# USB_Isolation.net
KiCad netlist of a schematic drawn in Altium Designer
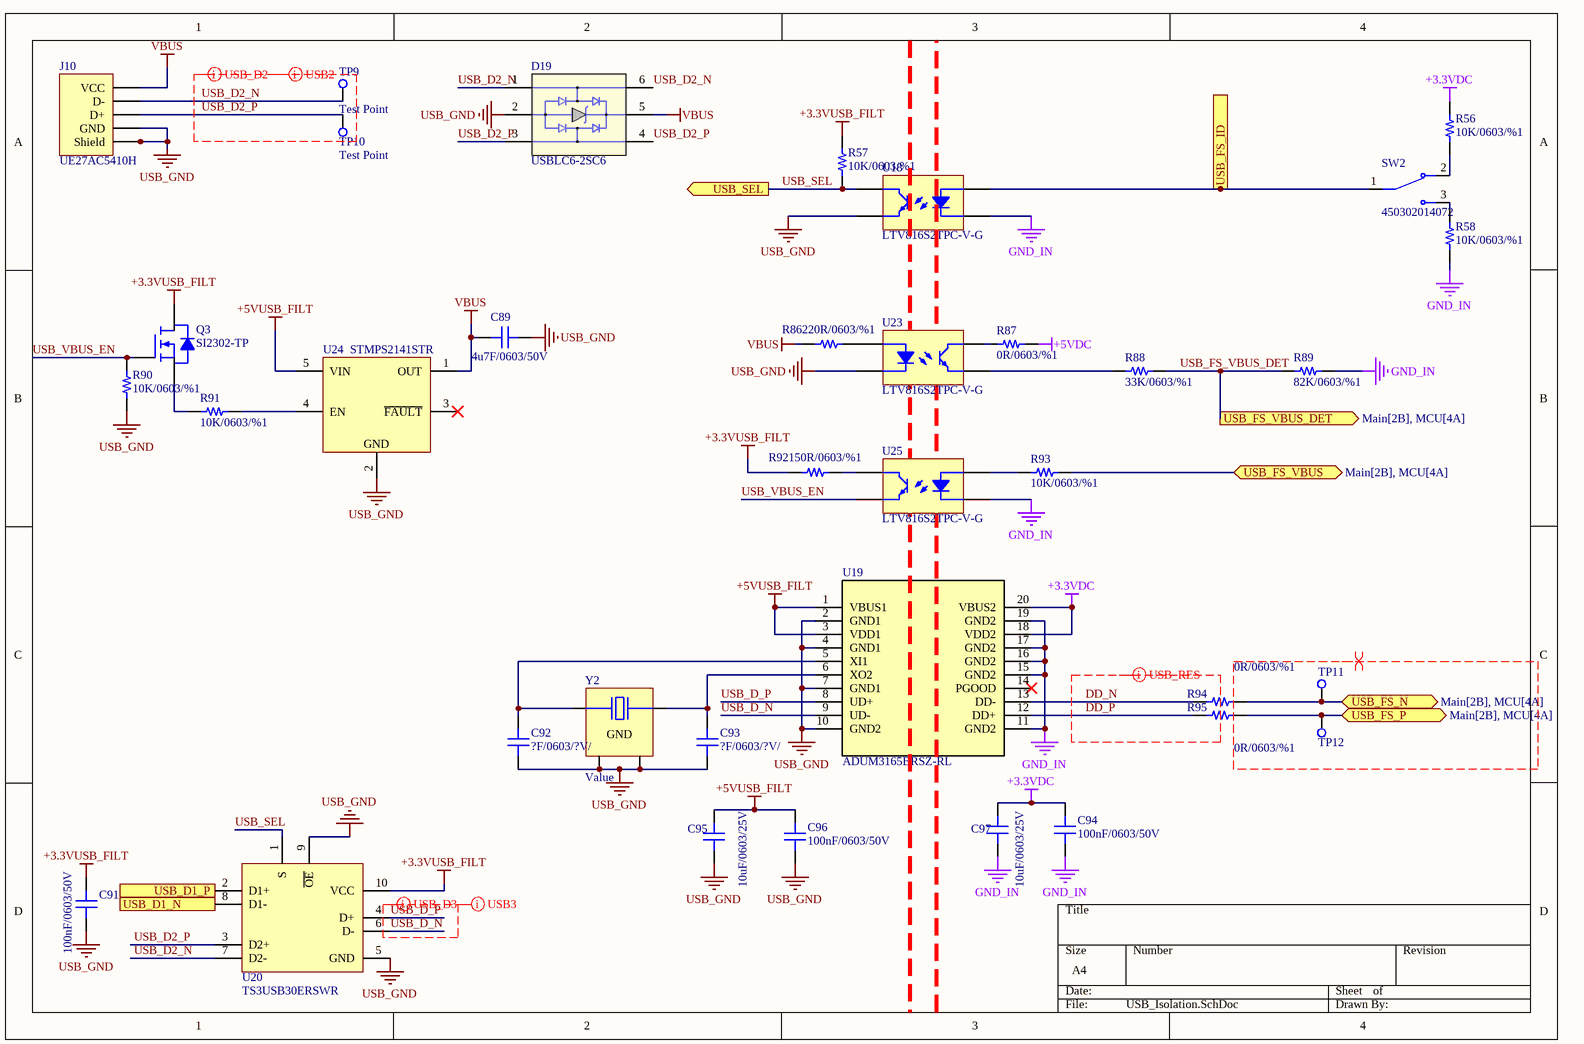
[diagram p0: USB_Isolation.SchDoc]

(export (version "E")
  (design (tool "Eeschema 10.0.6"))
  (components
    (comp (ref "C89")
      (value "4u7F/0603/50V")
      (footprint "0603_cap")
      (libsource (lib "IM_v1.0") (part "Capacitor"))
    )
    (comp (ref "C91")
      (value "100nF/0603/50V")
      (footprint "0603_cap")
      (libsource (lib "IM_v1.0") (part "Capacitor"))
    )
    (comp (ref "C92")
      (value "?F/0603/?V/")
      (footprint "0603_cap")
      (libsource (lib "IM_v1.0") (part "Capacitor"))
    )
    (comp (ref "C93")
      (value "?F/0603/?V/")
      (footprint "0603_cap")
      (libsource (lib "IM_v1.0") (part "Capacitor"))
    )
    (comp (ref "C94")
      (value "100nF/0603/50V")
      (footprint "0603_cap")
      (libsource (lib "IM_v1.0") (part "Capacitor"))
    )
    (comp (ref "C95")
      (value "10uF/0603/25V")
      (footprint "0603_cap")
      (libsource (lib "IM_v1.0") (part "Capacitor"))
    )
    (comp (ref "C96")
      (value "100nF/0603/50V")
      (footprint "0603_cap")
      (libsource (lib "IM_v1.0") (part "Capacitor"))
    )
    (comp (ref "C97")
      (value "10uF/0603/25V")
      (footprint "0603_cap")
      (libsource (lib "IM_v1.0") (part "Capacitor"))
    )
    (comp (ref "D19")
      (value "USBLC6-2SC6")
      (footprint "TI SOT-23-6 DBV")
      (description "17V Clamp 5A (8/20µs) Ipp Tvs Diode Surface Mount SOT-23-6")
      (libsource (lib "IM_v1.0") (part "USBLC6-2SC6"))
    )
    (comp (ref "J10")
      (value "UE27AC5410H")
      (footprint "UE27AC5410H")
      (libsource (lib "IM_v1.0") (part "USB 2.0 TYPE A"))
    )
    (comp (ref "Q3")
      (value "SI2302-TP")
      (footprint "TI SOT-23-3 DBZ")
      (description "MOSFET N-CH 20V 3A SOT-23")
      (libsource (lib "IM_v1.0") (part "N-CHN MOS SOT"))
    )
    (comp (ref "R56") (value "10K/0603/%1") (footprint "0603_res") (libsource (lib "IM_v1.0") (part "RES")))
    (comp (ref "R57") (value "10K/0603/%1") (footprint "0603_res") (libsource (lib "IM_v1.0") (part "RES")))
    (comp (ref "R58") (value "10K/0603/%1") (footprint "0603_res") (libsource (lib "IM_v1.0") (part "RES")))
    (comp (ref "R86") (value "220R/0603/%1") (footprint "0603_res") (libsource (lib "IM_v1.0") (part "RES")))
    (comp (ref "R87") (value "0R/0603/%1") (footprint "0603_res") (libsource (lib "IM_v1.0") (part "RES")))
    (comp (ref "R88") (value "33K/0603/%1") (footprint "0603_res") (libsource (lib "IM_v1.0") (part "RES")))
    (comp (ref "R89") (value "82K/0603/%1") (footprint "0603_res") (libsource (lib "IM_v1.0") (part "RES")))
    (comp (ref "R90") (value "10K/0603/%1") (footprint "0603_res") (libsource (lib "IM_v1.0") (part "RES")))
    (comp (ref "R91") (value "10K/0603/%1") (footprint "0603_res") (libsource (lib "IM_v1.0") (part "RES")))
    (comp (ref "R92") (value "150R/0603/%1") (footprint "0603_res") (libsource (lib "IM_v1.0") (part "RES")))
    (comp (ref "R93") (value "10K/0603/%1") (footprint "0603_res") (libsource (lib "IM_v1.0") (part "RES")))
    (comp (ref "R94") (value "0R/0603/%1") (footprint "0603_res") (libsource (lib "IM_v1.0") (part "RES")))
    (comp (ref "R95") (value "0R/0603/%1") (footprint "0603_res") (libsource (lib "IM_v1.0") (part "RES")))
    (comp (ref "SW2")
      (value "450302014072")
      (footprint "450302014072")
      (libsource (lib "IM_v1.0") (part "SPDT"))
    )
    (comp (ref "TP9") (value "Test Point") (footprint "tp") (libsource (lib "IM_v1.0") (part "Test Point")))
    (comp (ref "TP10") (value "Test Point") (footprint "tp") (libsource (lib "IM_v1.0") (part "Test Point")))
    (comp (ref "TP11") (value "Test Point") (footprint "tp") (libsource (lib "IM_v1.0") (part "Test Point")))
    (comp (ref "TP12") (value "Test Point") (footprint "tp") (libsource (lib "IM_v1.0") (part "Test Point")))
    (comp (ref "U18")
      (value "LTV816S2TPC-V-G")
      (footprint "4-SMD, Gull Wing")
      (libsource (lib "IM_v1.0") (part "OPTO"))
    )
    (comp (ref "U19")
      (value "ADUM3165BRSZ-RL")
      (footprint "SSOP-20")
      (description "3.75 kV RMS Digital Isolators for Isolated USB 2.0 High, Full, and Low Speed")
      (libsource (lib "IM_v1.0") (part "ADUM3165"))
    )
    (comp (ref "U20")
      (value "TS3USB30ERSWR")
      (footprint "VSSOP-10")
      (libsource (lib "IM_v1.0") (part "TS3USB30ERSWR"))
    )
    (comp (ref "U23")
      (value "LTV816S2TPC-V-G")
      (footprint "4-SMD, Gull Wing")
      (libsource (lib "") (part "OPTO_1"))
    )
    (comp (ref "U24")
      (value "STMPS2141STR")
      (footprint "SOT-23-5")
      (description "IC PWR SWITCH N-CHAN 1:1 SOT23-5")
      (fields (field (name "MANUFACTURER") "STMicroelectronics"))
      (libsource (lib "IM_v1.0") (part "STMPS2141STR"))
    )
    (comp (ref "U25")
      (value "LTV816S2TPC-V-G")
      (footprint "4-SMD, Gull Wing")
      (libsource (lib "IM_v1.0") (part "OPTO"))
    )
    (comp (ref "Y2")
      (value "Value")
      (footprint "SMD4-Nolead")
      (description "25 MHz ±10ppm Crystal 10pF 50 Ohms 4-SMD, No Lead")
      (libsource (lib "IM_v1.0") (part "Crystal(4-SMD)"))
    )
  )
  (nets
    (net (code "1") (name "+3.3VDC") (class "Default")
      (node (ref "C94") (pin "2") (pinfunction "2_2") (pintype "passive"))
      (node (ref "C97") (pin "2") (pinfunction "2_2") (pintype "passive"))
      (node (ref "R56") (pin "1") (pinfunction "1_1") (pintype "passive"))
      (node (ref "U19") (pin "18") (pinfunction "VDD2_18") (pintype "passive"))
      (node (ref "U19") (pin "20") (pinfunction "VBUS2_20") (pintype "passive"))
    )
    (net (code "2") (name "+3.3VUSB_FILT") (class "Default")
      (node (ref "C91") (pin "1") (pinfunction "1_1") (pintype "passive"))
      (node (ref "Q3") (pin "3") (pinfunction "D_3") (pintype "passive"))
      (node (ref "R57") (pin "1") (pinfunction "1_1") (pintype "passive"))
      (node (ref "R92") (pin "1") (pinfunction "1_1") (pintype "passive"))
      (node (ref "U20") (pin "10") (pinfunction "VCC_10") (pintype "passive"))
    )
    (net (code "3") (name "+5VDC") (class "Default")
      (node (ref "R87") (pin "1") (pinfunction "1_1") (pintype "passive"))
    )
    (net (code "4") (name "+5VUSB_FILT") (class "Default")
      (node (ref "C95") (pin "2") (pinfunction "2_2") (pintype "passive"))
      (node (ref "C96") (pin "2") (pinfunction "2_2") (pintype "passive"))
      (node (ref "U19") (pin "1") (pinfunction "VBUS1_1") (pintype "passive"))
      (node (ref "U19") (pin "3") (pinfunction "VDD1_3") (pintype "passive"))
      (node (ref "U24") (pin "5") (pinfunction "VIN_5") (pintype "passive"))
    )
    (net (code "5") (name "/DD_N") (class "Default")
      (node (ref "R94") (pin "2") (pinfunction "2_2") (pintype "passive"))
      (node (ref "U19") (pin "13") (pinfunction "DD-_13") (pintype "passive"))
    )
    (net (code "6") (name "/DD_P") (class "Default")
      (node (ref "R95") (pin "2") (pinfunction "2_2") (pintype "passive"))
      (node (ref "U19") (pin "12") (pinfunction "DD+_12") (pintype "passive"))
    )
    (net (code "7") (name "/USB_D1_N") (class "Default")
      (node (ref "U20") (pin "8") (pinfunction "D1-_8") (pintype "passive"))
    )
    (net (code "8") (name "/USB_D1_P") (class "Default")
      (node (ref "U20") (pin "2") (pinfunction "D1+_2") (pintype "passive"))
    )
    (net (code "9") (name "/USB_D2_N") (class "Default")
      (node (ref "D19") (pin "1") (pinfunction "1_1") (pintype "passive"))
      (node (ref "D19") (pin "6") (pinfunction "6_6") (pintype "passive"))
      (node (ref "J10") (pin "02") (pinfunction "D-_02") (pintype "passive"))
      (node (ref "TP9") (pin "1") (pinfunction "TP_1") (pintype "passive"))
      (node (ref "U20") (pin "7") (pinfunction "D2-_7") (pintype "passive"))
    )
    (net (code "10") (name "/USB_D2_P") (class "Default")
      (node (ref "D19") (pin "3") (pinfunction "3_3") (pintype "passive"))
      (node (ref "D19") (pin "4") (pinfunction "4_4") (pintype "passive"))
      (node (ref "J10") (pin "03") (pinfunction "D+_03") (pintype "passive"))
      (node (ref "TP10") (pin "1") (pinfunction "TP_1") (pintype "passive"))
      (node (ref "U20") (pin "3") (pinfunction "D2+_3") (pintype "passive"))
    )
    (net (code "11") (name "/USB_D_N") (class "Default")
      (node (ref "U19") (pin "9") (pinfunction "UD-_9") (pintype "passive"))
      (node (ref "U20") (pin "6") (pinfunction "D-_6") (pintype "passive"))
    )
    (net (code "12") (name "/USB_D_P") (class "Default")
      (node (ref "U19") (pin "8") (pinfunction "UD+_8") (pintype "passive"))
      (node (ref "U20") (pin "4") (pinfunction "D+_4") (pintype "passive"))
    )
    (net (code "13") (name "/USB_FS_ID") (class "Default")
      (node (ref "SW2") (pin "1") (pinfunction "1_1") (pintype "passive"))
      (node (ref "U18") (pin "1") (pinfunction "1_1") (pintype "passive"))
    )
    (net (code "14") (name "/USB_FS_N") (class "Default")
      (node (ref "R94") (pin "1") (pinfunction "1_1") (pintype "passive"))
      (node (ref "TP11") (pin "1") (pinfunction "TP_1") (pintype "passive"))
    )
    (net (code "15") (name "/USB_FS_P") (class "Default")
      (node (ref "R95") (pin "1") (pinfunction "1_1") (pintype "passive"))
      (node (ref "TP12") (pin "1") (pinfunction "TP_1") (pintype "passive"))
    )
    (net (code "16") (name "/USB_FS_VBUS") (class "Default")
      (node (ref "R93") (pin "1") (pinfunction "1_1") (pintype "passive"))
    )
    (net (code "17") (name "/USB_FS_VBUS_DET") (class "Default")
      (node (ref "R88") (pin "2") (pinfunction "2_2") (pintype "passive"))
      (node (ref "R89") (pin "1") (pinfunction "1_1") (pintype "passive"))
    )
    (net (code "18") (name "/USB_SEL") (class "Default")
      (node (ref "R57") (pin "2") (pinfunction "2_2") (pintype "passive"))
      (node (ref "U18") (pin "4") (pinfunction "4_4") (pintype "passive"))
      (node (ref "U20") (pin "1") (pinfunction "S_1") (pintype "passive"))
    )
    (net (code "19") (name "/USB_VBUS_EN") (class "Default")
      (node (ref "Q3") (pin "1") (pinfunction "G_1") (pintype "passive"))
      (node (ref "R90") (pin "2") (pinfunction "2_2") (pintype "passive"))
      (node (ref "U25") (pin "3") (pinfunction "3_3") (pintype "passive"))
    )
    (net (code "20") (name "GND_IN") (class "Default")
      (node (ref "C94") (pin "1") (pinfunction "1_1") (pintype "passive"))
      (node (ref "C97") (pin "1") (pinfunction "1_1") (pintype "passive"))
      (node (ref "R58") (pin "2") (pinfunction "2_2") (pintype "passive"))
      (node (ref "R89") (pin "2") (pinfunction "2_2") (pintype "passive"))
      (node (ref "U18") (pin "2") (pinfunction "2_2") (pintype "passive"))
      (node (ref "U19") (pin "11") (pinfunction "GND2_11") (pintype "passive"))
      (node (ref "U19") (pin "15") (pinfunction "GND2_15") (pintype "passive"))
      (node (ref "U19") (pin "16") (pinfunction "GND2_16") (pintype "passive"))
      (node (ref "U19") (pin "17") (pinfunction "GND2_17") (pintype "passive"))
      (node (ref "U19") (pin "19") (pinfunction "GND2_19") (pintype "passive"))
      (node (ref "U25") (pin "2") (pinfunction "2_2") (pintype "passive"))
    )
    (net (code "21") (name "Net-(Q3-S)") (class "Default")
      (node (ref "Q3") (pin "2") (pinfunction "S_2") (pintype "passive"))
      (node (ref "R91") (pin "1") (pinfunction "1_1") (pintype "passive"))
    )
    (net (code "22") (name "Net-(R56-Pad2)") (class "Default")
      (node (ref "R56") (pin "2") (pinfunction "2_2") (pintype "passive"))
      (node (ref "SW2") (pin "2") (pinfunction "2_2") (pintype "passive"))
    )
    (net (code "23") (name "Net-(R58-Pad1)") (class "Default")
      (node (ref "R58") (pin "1") (pinfunction "1_1") (pintype "passive"))
      (node (ref "SW2") (pin "3") (pinfunction "3_3") (pintype "passive"))
    )
    (net (code "24") (name "Net-(R86-Pad2)") (class "Default")
      (node (ref "R86") (pin "2") (pinfunction "2_2") (pintype "passive"))
      (node (ref "U23") (pin "1") (pinfunction "1_1") (pintype "passive"))
    )
    (net (code "25") (name "Net-(R87-Pad2)") (class "Default")
      (node (ref "R87") (pin "2") (pinfunction "2_2") (pintype "passive"))
      (node (ref "U23") (pin "4") (pinfunction "4_4") (pintype "passive"))
    )
    (net (code "26") (name "Net-(R88-Pad1)") (class "Default")
      (node (ref "R88") (pin "1") (pinfunction "1_1") (pintype "passive"))
      (node (ref "U23") (pin "3") (pinfunction "3_3") (pintype "passive"))
    )
    (net (code "27") (name "Net-(R92-Pad2)") (class "Default")
      (node (ref "R92") (pin "2") (pinfunction "2_2") (pintype "passive"))
      (node (ref "U25") (pin "4") (pinfunction "4_4") (pintype "passive"))
    )
    (net (code "28") (name "Net-(R93-Pad2)") (class "Default")
      (node (ref "R93") (pin "2") (pinfunction "2_2") (pintype "passive"))
      (node (ref "U25") (pin "1") (pinfunction "1_1") (pintype "passive"))
    )
    (net (code "29") (name "Net-(U19-XI1)") (class "Default")
      (node (ref "C92") (pin "2") (pinfunction "2_2") (pintype "passive"))
      (node (ref "U19") (pin "5") (pinfunction "XI1_5") (pintype "passive"))
      (node (ref "Y2") (pin "1") (pinfunction "1_1") (pintype "passive"))
    )
    (net (code "30") (name "Net-(U19-XO2)") (class "Default")
      (node (ref "C93") (pin "2") (pinfunction "2_2") (pintype "passive"))
      (node (ref "U19") (pin "6") (pinfunction "XO2_6") (pintype "passive"))
      (node (ref "Y2") (pin "3") (pinfunction "3_3") (pintype "passive"))
    )
    (net (code "31") (name "Net-(U24-EN)") (class "Default")
      (node (ref "R91") (pin "2") (pinfunction "2_2") (pintype "passive"))
      (node (ref "U24") (pin "4") (pinfunction "EN_4") (pintype "passive"))
    )
    (net (code "32") (name "USB_GND") (class "Default")
      (node (ref "C89") (pin "2") (pinfunction "2_2") (pintype "passive"))
      (node (ref "C91") (pin "2") (pinfunction "2_2") (pintype "passive"))
      (node (ref "C92") (pin "1") (pinfunction "1_1") (pintype "passive"))
      (node (ref "C93") (pin "1") (pinfunction "1_1") (pintype "passive"))
      (node (ref "C95") (pin "1") (pinfunction "1_1") (pintype "passive"))
      (node (ref "C96") (pin "1") (pinfunction "1_1") (pintype "passive"))
      (node (ref "D19") (pin "2") (pinfunction "2_2") (pintype "passive"))
      (node (ref "J10") (pin "04") (pinfunction "GND_04") (pintype "passive"))
      (node (ref "J10") (pin "S1") (pinfunction "Shield_S1") (pintype "passive"))
      (node (ref "J10") (pin "S2") (pinfunction "Shield_S2") (pintype "passive"))
      (node (ref "R90") (pin "1") (pinfunction "1_1") (pintype "passive"))
      (node (ref "U18") (pin "3") (pinfunction "3_3") (pintype "passive"))
      (node (ref "U19") (pin "10") (pinfunction "GND2_10") (pintype "passive"))
      (node (ref "U19") (pin "2") (pinfunction "GND1_2") (pintype "passive"))
      (node (ref "U19") (pin "4") (pinfunction "GND1_4") (pintype "passive"))
      (node (ref "U19") (pin "7") (pinfunction "GND1_7") (pintype "passive"))
      (node (ref "U20") (pin "5") (pinfunction "GND_5") (pintype "passive"))
      (node (ref "U20") (pin "9") (pinfunction "~{OE}_9") (pintype "passive"))
      (node (ref "U23") (pin "2") (pinfunction "2_2") (pintype "passive"))
      (node (ref "U24") (pin "2") (pinfunction "GND_2") (pintype "passive"))
      (node (ref "Y2") (pin "2") (pinfunction "GND_2") (pintype "passive"))
      (node (ref "Y2") (pin "4") (pinfunction "GND_4") (pintype "passive"))
    )
    (net (code "33") (name "VBUS") (class "Default")
      (node (ref "C89") (pin "1") (pinfunction "1_1") (pintype "passive"))
      (node (ref "D19") (pin "5") (pinfunction "5_5") (pintype "passive"))
      (node (ref "J10") (pin "01") (pinfunction "VCC_01") (pintype "passive"))
      (node (ref "R86") (pin "1") (pinfunction "1_1") (pintype "passive"))
      (node (ref "U24") (pin "1") (pinfunction "OUT_1") (pintype "passive"))
    )
    (net (code "34") (name "unconnected-(U19-PGOOD-Pad14)") (class "Default")
      (node (ref "U19") (pin "14") (pinfunction "PGOOD_14") (pintype "passive+no_connect"))
    )
    (net (code "35") (name "unconnected-(U24-~{FAULT}-Pad3)") (class "Default")
      (node (ref "U24") (pin "3") (pinfunction "~{FAULT}_3") (pintype "passive+no_connect"))
    )
  )
)
